# hv_top.net
KiCad netlist of a schematic drawn in Altium Designer
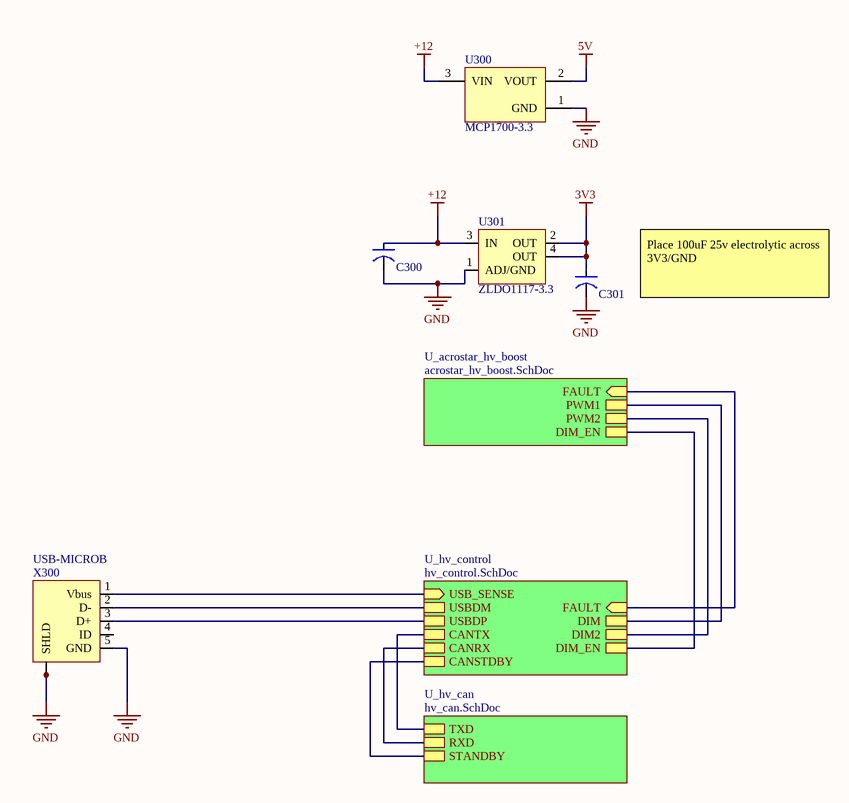
[diagram p0: hv_top.SchDoc]

(export (version "E")
  (design (tool "Eeschema 10.0.6"))
  (components
    (comp (ref "C300")
      (value "CAP 4.7uF 25V TANT 2312")
      (footprint "CAPMP6032X28M")
      (description "CAPACITOR TANT, 4.7UF, 25V, 10%, REEL")
      (fields (field (name "VOLTAGE") "25V") (field (name "TOLERANCE") "10%"))
      (libsource (lib "StackFoundry LLC") (part "CAP 4.7uF 25V TANT 2312"))
    )
    (comp (ref "C301")
      (value "CAP 4.7uF 25V TANT 2312")
      (footprint "CAPMP6032X28M")
      (description "CAPACITOR TANT, 4.7UF, 25V, 10%, REEL")
      (fields (field (name "VOLTAGE") "25V") (field (name "TOLERANCE") "10%"))
      (libsource (lib "StackFoundry LLC") (part "CAP 4.7uF 25V TANT 2312"))
    )
    (comp (ref "U300")
      (value "MCP1700-3.3")
      (footprint "SOT-23-TT3_N")
      (description "Pwr Sply Func; Voltage Regulator; LDO; SOT-23; PD 369.6mW; VO 3.3V; Regline +/-0.75%/V")
      (libsource (lib "StackFoundry LLC") (part "PM-LINEREG-MCP1700-IL3"))
    )
    (comp (ref "U301")
      (value "ZLDO1117-3.3")
      (footprint "SOT223")
      (fields (field (name "SOURCE") "vreg.SchLib"))
      (libsource (lib "StackFoundry LLC") (part "ZLDO1117-3.3"))
    )
    (comp (ref "X300")
      (value "USB-MICROB")
      (footprint "FCI-10118193-0001LF")
      (libsource (lib "StackFoundry LLC") (part "USB-MICROB"))
    )
  )
  (nets
    (net (code "1") (name "+12") (class "Default")
      (node (ref "C300") (pin "1") (pintype "passive"))
      (node (ref "U300") (pin "3") (pinfunction "VIN_3") (pintype "power_in"))
      (node (ref "U301") (pin "3") (pinfunction "IN_3") (pintype "passive"))
    )
    (net (code "9") (name "/USBDM") (class "Default")
      (node (ref "X300") (pin "2") (pinfunction "D-_2") (pintype "passive"))
    )
    (net (code "10") (name "/USBDP") (class "Default")
      (node (ref "X300") (pin "3") (pinfunction "D+_3") (pintype "passive"))
    )
    (net (code "11") (name "/USB_SENSE") (class "Default")
      (node (ref "X300") (pin "1") (pinfunction "Vbus_1") (pintype "passive"))
    )
    (net (code "12") (name "3V3") (class "Default")
      (node (ref "C301") (pin "1") (pintype "passive"))
      (node (ref "U301") (pin "2") (pinfunction "OUT_2") (pintype "power_in"))
      (node (ref "U301") (pin "4") (pinfunction "OUT_4") (pintype "power_in"))
    )
    (net (code "13") (name "5V") (class "Default")
      (node (ref "U300") (pin "2") (pinfunction "VOUT_2") (pintype "power_in"))
    )
    (net (code "14") (name "GND") (class "Default")
      (node (ref "C300") (pin "2") (pintype "passive"))
      (node (ref "C301") (pin "2") (pintype "passive"))
      (node (ref "U300") (pin "1") (pinfunction "GND_1") (pintype "power_in"))
      (node (ref "U301") (pin "1") (pinfunction "ADJ/GND_1") (pintype "passive"))
      (node (ref "X300") (pin "5") (pinfunction "GND_5") (pintype "passive"))
      (node (ref "X300") (pin "G1") (pinfunction "G1_G1") (pintype "passive"))
      (node (ref "X300") (pin "G2") (pinfunction "G2_G2") (pintype "passive"))
      (node (ref "X300") (pin "G3") (pinfunction "G3_G3") (pintype "passive"))
      (node (ref "X300") (pin "G4") (pinfunction "G4_G4") (pintype "passive"))
      (node (ref "X300") (pin "T1") (pinfunction "SHLD_T1") (pintype "passive"))
      (node (ref "X300") (pin "T2") (pinfunction "T2_T2") (pintype "passive"))
    )
    (net (code "15") (name "unconnected-(X300-ID-Pad4)") (class "Default")
      (node (ref "X300") (pin "4") (pinfunction "ID_4") (pintype "passive"))
    )
  )
)
